# MPPT_V1_0_1_MCU_and_Display.net
KiCad netlist of a schematic drawn in Altium Designer
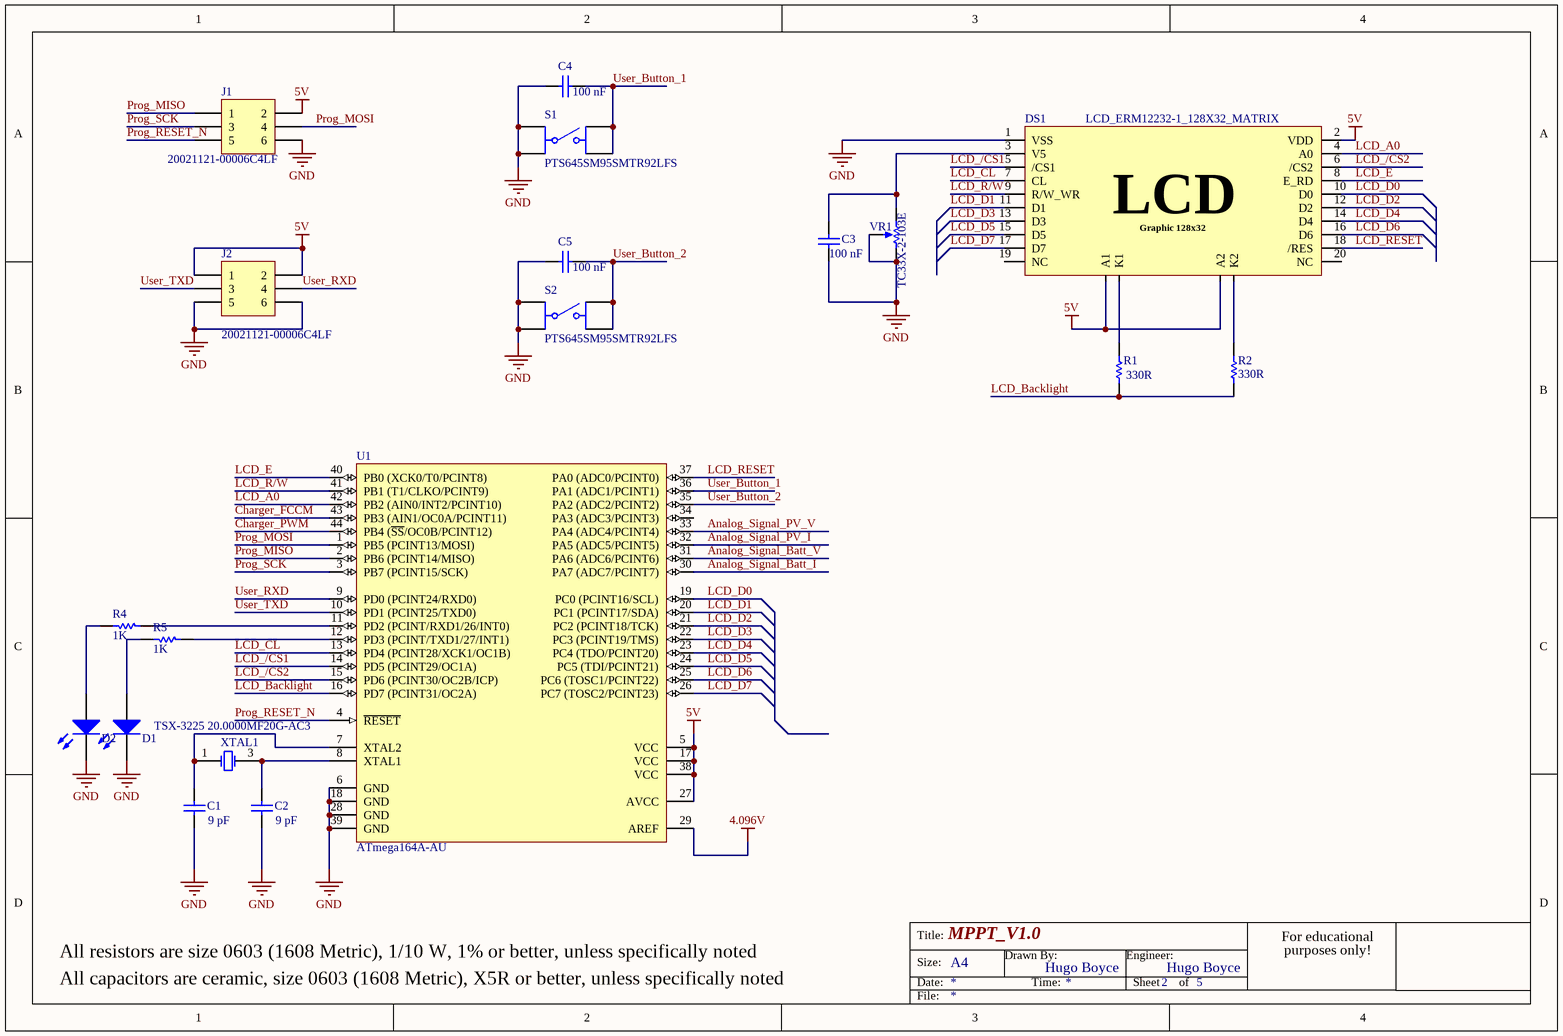
[diagram p0: MPPT_V1.0.1_MCU_and_Display.SchDoc]

(export (version "E")
  (design (tool "Eeschema 10.0.6"))
  (components
    (comp (ref "C1")
      (value "9 pF")
      (footprint "CAPC1608N")
      (description "Capacitor")
      (fields (field (name "Comment") "Cap SMD") (field (name "PUBLISHER") "Altium Limited"))
      (libsource (lib "Miscellaneous Devices") (part "Cap SMD"))
    )
    (comp (ref "C2")
      (value "9 pF")
      (footprint "CAPC1608N")
      (description "Capacitor")
      (fields (field (name "Comment") "Cap SMD") (field (name "PUBLISHER") "Altium Limited"))
      (libsource (lib "Miscellaneous Devices") (part "Cap SMD"))
    )
    (comp (ref "C3")
      (value "100 nF")
      (footprint "CAPC1608N")
      (description "Capacitor")
      (fields (field (name "Comment") "Cap SMD") (field (name "PUBLISHER") "Altium Limited"))
      (libsource (lib "Miscellaneous Devices") (part "Cap SMD"))
    )
    (comp (ref "C4")
      (value "100 nF")
      (footprint "CAPC1608N")
      (description "Capacitor")
      (fields (field (name "Comment") "Cap SMD") (field (name "PUBLISHER") "Altium Limited"))
      (libsource (lib "Miscellaneous Devices") (part "Cap SMD"))
    )
    (comp (ref "C5")
      (value "100 nF")
      (footprint "CAPC1608N")
      (description "Capacitor")
      (fields (field (name "Comment") "Cap SMD") (field (name "PUBLISHER") "Altium Limited"))
      (libsource (lib "Miscellaneous Devices") (part "Cap SMD"))
    )
    (comp (ref "D1")
      (value "150120RS75000")
      (footprint "150120RS75000")
      (description "LED RED CLEAR 1206 SMD")
      (fields (field (name "MANUFACTURER") "Wurth Electronics Inc."))
      (libsource (lib "MPPT_SCH_Library") (part "150120RS75000"))
    )
    (comp (ref "D2")
      (value "150120RS75000")
      (footprint "150120RS75000")
      (description "LED RED CLEAR 1206 SMD")
      (fields (field (name "MANUFACTURER") "Wurth Electronics Inc."))
      (libsource (lib "MPPT_SCH_Library") (part "150120RS75000"))
    )
    (comp (ref "DS1")
      (value "LCD_ERM12232-1_128X32_MATRIX")
      (footprint "LCD_ERM12232")
      (description "128x64 Graphic LCD Module, EastRising")
      (libsource (lib "MPPT_SCH_Library") (part "LCD_ERM12232-1_128X64_MATRIX"))
    )
    (comp (ref "J1")
      (value "20021121-00006C4LF")
      (footprint "20021121-00006")
      (description "CONN HEADER 6POS DL UNSHRD SMD")
      (fields
        (field (name "MANUFACTURER") "Amphenol FCI")
        (field (name "MANUFACTURER PART NUMBER") "20021121-00006C4LF")
      )
      (libsource (lib "MPPT_SCH_Library") (part "20021121-00006C4LF"))
    )
    (comp (ref "J2")
      (value "20021121-00006C4LF")
      (footprint "20021121-00006")
      (description "CONN HEADER 6POS DL UNSHRD SMD")
      (fields
        (field (name "MANUFACTURER") "Amphenol FCI")
        (field (name "MANUFACTURER PART NUMBER") "20021121-00006C4LF")
      )
      (libsource (lib "MPPT_SCH_Library") (part "20021121-00006C4LF"))
    )
    (comp (ref "R1")
      (value "330R")
      (footprint "RESC1608N")
      (description "Resistor")
      (fields (field (name "Comment") "Res SMD") (field (name "PUBLISHER") "Altium Limited"))
      (libsource (lib "Miscellaneous Devices") (part "Res SMD"))
    )
    (comp (ref "R2")
      (value "330R")
      (footprint "RESC1608N")
      (description "Resistor")
      (fields (field (name "Comment") "Res SMD") (field (name "PUBLISHER") "Altium Limited"))
      (libsource (lib "Miscellaneous Devices") (part "Res SMD"))
    )
    (comp (ref "R4")
      (value "1K")
      (footprint "RESC1608N")
      (description "Resistor")
      (fields (field (name "Comment") "Res SMD") (field (name "PUBLISHER") "Altium Limited"))
      (libsource (lib "Miscellaneous Devices") (part "Res SMD"))
    )
    (comp (ref "R5")
      (value "1K")
      (footprint "RESC1608N")
      (description "Resistor")
      (fields (field (name "Comment") "Res SMD") (field (name "PUBLISHER") "Altium Limited"))
      (libsource (lib "Miscellaneous Devices") (part "Res SMD"))
    )
    (comp (ref "S1")
      (value "PTS645SM95SMTR92LFS")
      (footprint "PTS645SM95SMTR92LFS")
      (description "SWITCH TACTILE SPST-NO 0.05A 12V")
      (fields
        (field (name "MANUFACTURER") "C&K")
        (field (name "MANUFACTURER PART NUMBER") "PTS645SM95SMTR92LFS")
      )
      (libsource (lib "MPPT_SCH_Library") (part "PTS645SM95SMTR92LFS"))
    )
    (comp (ref "S2")
      (value "PTS645SM95SMTR92LFS")
      (footprint "PTS645SM95SMTR92LFS")
      (description "SWITCH TACTILE SPST-NO 0.05A 12V")
      (fields
        (field (name "MANUFACTURER") "C&K")
        (field (name "MANUFACTURER PART NUMBER") "PTS645SM95SMTR92LFS")
      )
      (libsource (lib "MPPT_SCH_Library") (part "PTS645SM95SMTR92LFS"))
    )
    (comp (ref "U1")
      (value "ATmega164A-AU")
      (footprint "44A_N")
      (fields (field (name "PUBLISHER") "Altium Limited"))
      (libsource (lib "Atmel Microcontroller 8-Bit megaAVR") (part "ATmega164A-AU"))
    )
    (comp (ref "VR1")
      (value "TC33X-2-103E")
      (footprint "TC33_BOURNS")
      (description "TRIMMER 10K OHM 0.1W SMD")
      (fields
        (field (name "MANUFACTURER") "Bourns Inc.")
        (field (name "TOLERANCE") "±25%")
        (field (name "MANUFACTURER PART NUMBER") "TC33X-2-103E")
      )
      (libsource (lib "MPPT_SCH_Library") (part "TC33X-2-103E"))
    )
    (comp (ref "XTAL1")
      (value "TSX-3225 20.0000MF20G-AC3")
      (footprint "EPSON_TSX-3225")
      (description "CRYSTAL 20.0000MHZ 9PF SMD")
      (fields
        (field (name "MANUFACTURER") "EPSON")
        (field (name "MANUFACTURER PART NUMBER") "TSX-3225 20.0000MF20G-AC3")
      )
      (libsource (lib "MPPT_SCH_Library") (part "TSX-3225 20.0000MF20G-AC3"))
    )
  )
  (nets
    (net (code "1") (name "/Analog_Signal_Batt_I") (class "Default")
      (node (ref "U1") (pin "30") (pinfunction "PA7_(ADC7/PCINT7)_30") (pintype "bidirectional"))
    )
    (net (code "2") (name "/Analog_Signal_Batt_V") (class "Default")
      (node (ref "U1") (pin "31") (pinfunction "PA6_(ADC6/PCINT6)_31") (pintype "bidirectional"))
    )
    (net (code "3") (name "/Analog_Signal_PV_I") (class "Default")
      (node (ref "U1") (pin "32") (pinfunction "PA5_(ADC5/PCINT5)_32") (pintype "bidirectional"))
    )
    (net (code "4") (name "/Analog_Signal_PV_V") (class "Default")
      (node (ref "U1") (pin "33") (pinfunction "PA4_(ADC4/PCINT4)_33") (pintype "bidirectional"))
    )
    (net (code "5") (name "/Charger_FCCM") (class "Default")
      (node (ref "U1") (pin "43") (pinfunction "PB3_(AIN1/OC0A/PCINT11)_43") (pintype "bidirectional"))
    )
    (net (code "6") (name "/Charger_PWM") (class "Default")
      (node (ref "U1") (pin "44") (pinfunction "PB4_(~{SS}/OC0B/PCINT12)_44") (pintype "bidirectional"))
    )
    (net (code "7") (name "/LCD_A0") (class "Default")
      (node (ref "DS1") (pin "4") (pinfunction "A0_4") (pintype "passive"))
      (node (ref "U1") (pin "42") (pinfunction "PB2_(AIN0/INT2/PCINT10)_42") (pintype "bidirectional"))
    )
    (net (code "8") (name "/LCD_Backlight") (class "Default")
      (node (ref "R1") (pin "1") (pinfunction "1_1") (pintype "passive"))
      (node (ref "R2") (pin "1") (pinfunction "1_1") (pintype "passive"))
      (node (ref "U1") (pin "16") (pinfunction "PD7_(PCINT31/OC2A)_16") (pintype "bidirectional"))
    )
    (net (code "9") (name "/LCD_CL") (class "Default")
      (node (ref "DS1") (pin "7") (pinfunction "CL_7") (pintype "passive"))
      (node (ref "U1") (pin "13") (pinfunction "PD4_(PCINT28/XCK1/OC1B)_13") (pintype "bidirectional"))
    )
    (net (code "10") (name "/LCD_D0") (class "Default")
      (node (ref "DS1") (pin "10") (pinfunction "D0_10") (pintype "passive"))
      (node (ref "U1") (pin "19") (pinfunction "PC0_(PCINT16/SCL)_19") (pintype "bidirectional"))
    )
    (net (code "11") (name "/LCD_D1") (class "Default")
      (node (ref "DS1") (pin "11") (pinfunction "D1_11") (pintype "passive"))
      (node (ref "U1") (pin "20") (pinfunction "PC1_(PCINT17/SDA)_20") (pintype "bidirectional"))
    )
    (net (code "12") (name "/LCD_D2") (class "Default")
      (node (ref "DS1") (pin "12") (pinfunction "D2_12") (pintype "passive"))
      (node (ref "U1") (pin "21") (pinfunction "PC2_(PCINT18/TCK)_21") (pintype "bidirectional"))
    )
    (net (code "13") (name "/LCD_D3") (class "Default")
      (node (ref "DS1") (pin "13") (pinfunction "D3_13") (pintype "passive"))
      (node (ref "U1") (pin "22") (pinfunction "PC3_(PCINT19/TMS)_22") (pintype "bidirectional"))
    )
    (net (code "14") (name "/LCD_D4") (class "Default")
      (node (ref "DS1") (pin "14") (pinfunction "D4_14") (pintype "passive"))
      (node (ref "U1") (pin "23") (pinfunction "PC4_(TDO/PCINT20)_23") (pintype "bidirectional"))
    )
    (net (code "15") (name "/LCD_D5") (class "Default")
      (node (ref "DS1") (pin "15") (pinfunction "D5_15") (pintype "passive"))
      (node (ref "U1") (pin "24") (pinfunction "PC5_(TDI/PCINT21)_24") (pintype "bidirectional"))
    )
    (net (code "16") (name "/LCD_D6") (class "Default")
      (node (ref "DS1") (pin "16") (pinfunction "D6_16") (pintype "passive"))
      (node (ref "U1") (pin "25") (pinfunction "PC6_(TOSC1/PCINT22)_25") (pintype "bidirectional"))
    )
    (net (code "17") (name "/LCD_D7") (class "Default")
      (node (ref "DS1") (pin "17") (pinfunction "D7_17") (pintype "passive"))
      (node (ref "U1") (pin "26") (pinfunction "PC7_(TOSC2/PCINT23)_26") (pintype "bidirectional"))
    )
    (net (code "18") (name "/LCD_E") (class "Default")
      (node (ref "DS1") (pin "8") (pinfunction "E_RD_8") (pintype "passive"))
      (node (ref "U1") (pin "40") (pinfunction "PB0_(XCK0/T0/PCINT8)_40") (pintype "bidirectional"))
    )
    (net (code "19") (name "/LCD_RESET") (class "Default")
      (node (ref "DS1") (pin "18") (pinfunction "/RES_18") (pintype "passive"))
      (node (ref "U1") (pin "37") (pinfunction "PA0_(ADC0/PCINT0)_37") (pintype "bidirectional"))
    )
    (net (code "20") (name "/LCD_R{slash}W") (class "Default")
      (node (ref "DS1") (pin "9") (pinfunction "R/W_WR_9") (pintype "passive"))
      (node (ref "U1") (pin "41") (pinfunction "PB1_(T1/CLKO/PCINT9)_41") (pintype "bidirectional"))
    )
    (net (code "21") (name "/LCD_{slash}CS1") (class "Default")
      (node (ref "DS1") (pin "5") (pinfunction "/CS1_5") (pintype "passive"))
      (node (ref "U1") (pin "14") (pinfunction "PD5_(PCINT29/OC1A)_14") (pintype "bidirectional"))
    )
    (net (code "22") (name "/LCD_{slash}CS2") (class "Default")
      (node (ref "DS1") (pin "6") (pinfunction "/CS2_6") (pintype "passive"))
      (node (ref "U1") (pin "15") (pinfunction "PD6_(PCINT30/OC2B/ICP)_15") (pintype "bidirectional"))
    )
    (net (code "23") (name "/Prog_MISO") (class "Default")
      (node (ref "J1") (pin "1") (pinfunction "1_1") (pintype "passive"))
      (node (ref "U1") (pin "2") (pinfunction "PB6_(PCINT14/MISO)_2") (pintype "bidirectional"))
    )
    (net (code "24") (name "/Prog_MOSI") (class "Default")
      (node (ref "J1") (pin "4") (pinfunction "4_4") (pintype "passive"))
      (node (ref "U1") (pin "1") (pinfunction "PB5_(PCINT13/MOSI)_1") (pintype "bidirectional"))
    )
    (net (code "25") (name "/Prog_RESET_N") (class "Default")
      (node (ref "J1") (pin "5") (pinfunction "5_5") (pintype "passive"))
      (node (ref "U1") (pin "4") (pinfunction "~{RESET}_4") (pintype "input"))
    )
    (net (code "26") (name "/Prog_SCK") (class "Default")
      (node (ref "J1") (pin "3") (pinfunction "3_3") (pintype "passive"))
      (node (ref "U1") (pin "3") (pinfunction "PB7_(PCINT15/SCK)_3") (pintype "bidirectional"))
    )
    (net (code "27") (name "/User_Button_1") (class "Default")
      (node (ref "C4") (pin "1") (pinfunction "1_1") (pintype "passive"))
      (node (ref "S1") (pin "2") (pinfunction "2_2") (pintype "passive"))
      (node (ref "S1") (pin "4") (pinfunction "4_4") (pintype "passive"))
      (node (ref "U1") (pin "36") (pinfunction "PA1_(ADC1/PCINT1)_36") (pintype "bidirectional"))
    )
    (net (code "28") (name "/User_Button_2") (class "Default")
      (node (ref "C5") (pin "1") (pinfunction "1_1") (pintype "passive"))
      (node (ref "S2") (pin "2") (pinfunction "2_2") (pintype "passive"))
      (node (ref "S2") (pin "4") (pinfunction "4_4") (pintype "passive"))
      (node (ref "U1") (pin "35") (pinfunction "PA2_(ADC2/PCINT2)_35") (pintype "bidirectional"))
    )
    (net (code "29") (name "/User_RXD") (class "Default")
      (node (ref "J2") (pin "4") (pinfunction "4_4") (pintype "passive"))
      (node (ref "U1") (pin "9") (pinfunction "PD0_(PCINT24/RXD0)_9") (pintype "bidirectional"))
    )
    (net (code "30") (name "/User_TXD") (class "Default")
      (node (ref "J2") (pin "3") (pinfunction "3_3") (pintype "passive"))
      (node (ref "U1") (pin "10") (pinfunction "PD1_(PCINT25/TXD0)_10") (pintype "bidirectional"))
    )
    (net (code "31") (name "4.096V") (class "Default")
      (node (ref "U1") (pin "29") (pinfunction "AREF_29") (pintype "power_in"))
    )
    (net (code "32") (name "5V") (class "Default")
      (node (ref "DS1") (pin "2") (pinfunction "VDD_2") (pintype "passive"))
      (node (ref "DS1") (pin "21") (pinfunction "A1_21") (pintype "passive"))
      (node (ref "DS1") (pin "23") (pinfunction "A2_23") (pintype "passive"))
      (node (ref "J1") (pin "2") (pinfunction "2_2") (pintype "passive"))
      (node (ref "J2") (pin "1") (pinfunction "1_1") (pintype "passive"))
      (node (ref "J2") (pin "2") (pinfunction "2_2") (pintype "passive"))
      (node (ref "U1") (pin "17") (pinfunction "VCC_17") (pintype "power_in"))
      (node (ref "U1") (pin "27") (pinfunction "AVCC_27") (pintype "power_in"))
      (node (ref "U1") (pin "38") (pinfunction "VCC_38") (pintype "power_in"))
      (node (ref "U1") (pin "5") (pinfunction "VCC_5") (pintype "power_in"))
    )
    (net (code "33") (name "GND") (class "Default")
      (node (ref "C1") (pin "1") (pinfunction "1_1") (pintype "passive"))
      (node (ref "C2") (pin "1") (pinfunction "1_1") (pintype "passive"))
      (node (ref "C3") (pin "1") (pinfunction "1_1") (pintype "passive"))
      (node (ref "C4") (pin "2") (pinfunction "2_2") (pintype "passive"))
      (node (ref "C5") (pin "2") (pinfunction "2_2") (pintype "passive"))
      (node (ref "D1") (pin "1") (pinfunction "K_1") (pintype "passive"))
      (node (ref "D2") (pin "1") (pinfunction "K_1") (pintype "passive"))
      (node (ref "DS1") (pin "1") (pinfunction "VSS_1") (pintype "passive"))
      (node (ref "J1") (pin "6") (pinfunction "6_6") (pintype "passive"))
      (node (ref "J2") (pin "5") (pinfunction "5_5") (pintype "passive"))
      (node (ref "J2") (pin "6") (pinfunction "6_6") (pintype "passive"))
      (node (ref "S1") (pin "1") (pinfunction "1_1") (pintype "passive"))
      (node (ref "S1") (pin "3") (pinfunction "3_3") (pintype "passive"))
      (node (ref "S2") (pin "1") (pinfunction "1_1") (pintype "passive"))
      (node (ref "S2") (pin "3") (pinfunction "3_3") (pintype "passive"))
      (node (ref "U1") (pin "18") (pinfunction "GND_18") (pintype "power_in"))
      (node (ref "U1") (pin "28") (pinfunction "GND_28") (pintype "power_in"))
      (node (ref "U1") (pin "39") (pinfunction "GND_39") (pintype "power_in"))
      (node (ref "U1") (pin "6") (pinfunction "GND_6") (pintype "power_in"))
      (node (ref "VR1") (pin "1") (pinfunction "CCW_1") (pintype "passive"))
      (node (ref "VR1") (pin "2") (pinfunction "WIPER_2") (pintype "passive"))
    )
    (net (code "34") (name "Net-(D1-A)") (class "Default")
      (node (ref "D1") (pin "2") (pinfunction "A_2") (pintype "passive"))
      (node (ref "R5") (pin "2") (pinfunction "2_2") (pintype "passive"))
    )
    (net (code "35") (name "Net-(D2-A)") (class "Default")
      (node (ref "D2") (pin "2") (pinfunction "A_2") (pintype "passive"))
      (node (ref "R4") (pin "2") (pinfunction "2_2") (pintype "passive"))
    )
    (net (code "36") (name "Net-(DS1-K1)") (class "Default")
      (node (ref "DS1") (pin "22") (pinfunction "K1_22") (pintype "passive"))
      (node (ref "R1") (pin "2") (pinfunction "2_2") (pintype "passive"))
    )
    (net (code "37") (name "Net-(DS1-K2)") (class "Default")
      (node (ref "DS1") (pin "24") (pinfunction "K2_24") (pintype "passive"))
      (node (ref "R2") (pin "2") (pinfunction "2_2") (pintype "passive"))
    )
    (net (code "38") (name "Net-(DS1-V5)") (class "Default")
      (node (ref "C3") (pin "2") (pinfunction "2_2") (pintype "passive"))
      (node (ref "DS1") (pin "3") (pinfunction "V5_3") (pintype "passive"))
      (node (ref "VR1") (pin "3") (pinfunction "CW_3") (pintype "passive"))
    )
    (net (code "39") (name "Net-(U1-PD2_(PCINT{slash}RXD1{slash}26{slash}INT0))") (class "Default")
      (node (ref "R4") (pin "1") (pinfunction "1_1") (pintype "passive"))
      (node (ref "U1") (pin "11") (pinfunction "PD2_(PCINT/RXD1/26/INT0)_11") (pintype "bidirectional"))
    )
    (net (code "40") (name "Net-(U1-PD3_(PCINT{slash}TXD1{slash}27{slash}INT1))") (class "Default")
      (node (ref "R5") (pin "1") (pinfunction "1_1") (pintype "passive"))
      (node (ref "U1") (pin "12") (pinfunction "PD3_(PCINT/TXD1/27/INT1)_12") (pintype "bidirectional"))
    )
    (net (code "41") (name "Net-(U1-XTAL1)") (class "Default")
      (node (ref "C2") (pin "2") (pinfunction "2_2") (pintype "passive"))
      (node (ref "U1") (pin "8") (pinfunction "XTAL1_8") (pintype "passive"))
      (node (ref "XTAL1") (pin "3") (pinfunction "OSC2_3") (pintype "passive"))
    )
    (net (code "42") (name "Net-(U1-XTAL2)") (class "Default")
      (node (ref "C1") (pin "2") (pinfunction "2_2") (pintype "passive"))
      (node (ref "U1") (pin "7") (pinfunction "XTAL2_7") (pintype "passive"))
      (node (ref "XTAL1") (pin "1") (pinfunction "OSC1_1") (pintype "passive"))
    )
    (net (code "43") (name "unconnected-(DS1-NC-Pad19)") (class "Default")
      (node (ref "DS1") (pin "19") (pinfunction "NC_19") (pintype "passive"))
    )
    (net (code "44") (name "unconnected-(DS1-NC-Pad20)") (class "Default")
      (node (ref "DS1") (pin "20") (pinfunction "NC_20") (pintype "passive"))
    )
    (net (code "45") (name "unconnected-(U1-PA3_(ADC3{slash}PCINT3)-Pad34)") (class "Default")
      (node (ref "U1") (pin "34") (pinfunction "PA3_(ADC3/PCINT3)_34") (pintype "bidirectional"))
    )
  )
)
